# 2_BLE-T1-matrix.net
KiCad netlist of a schematic drawn in Altium Designer
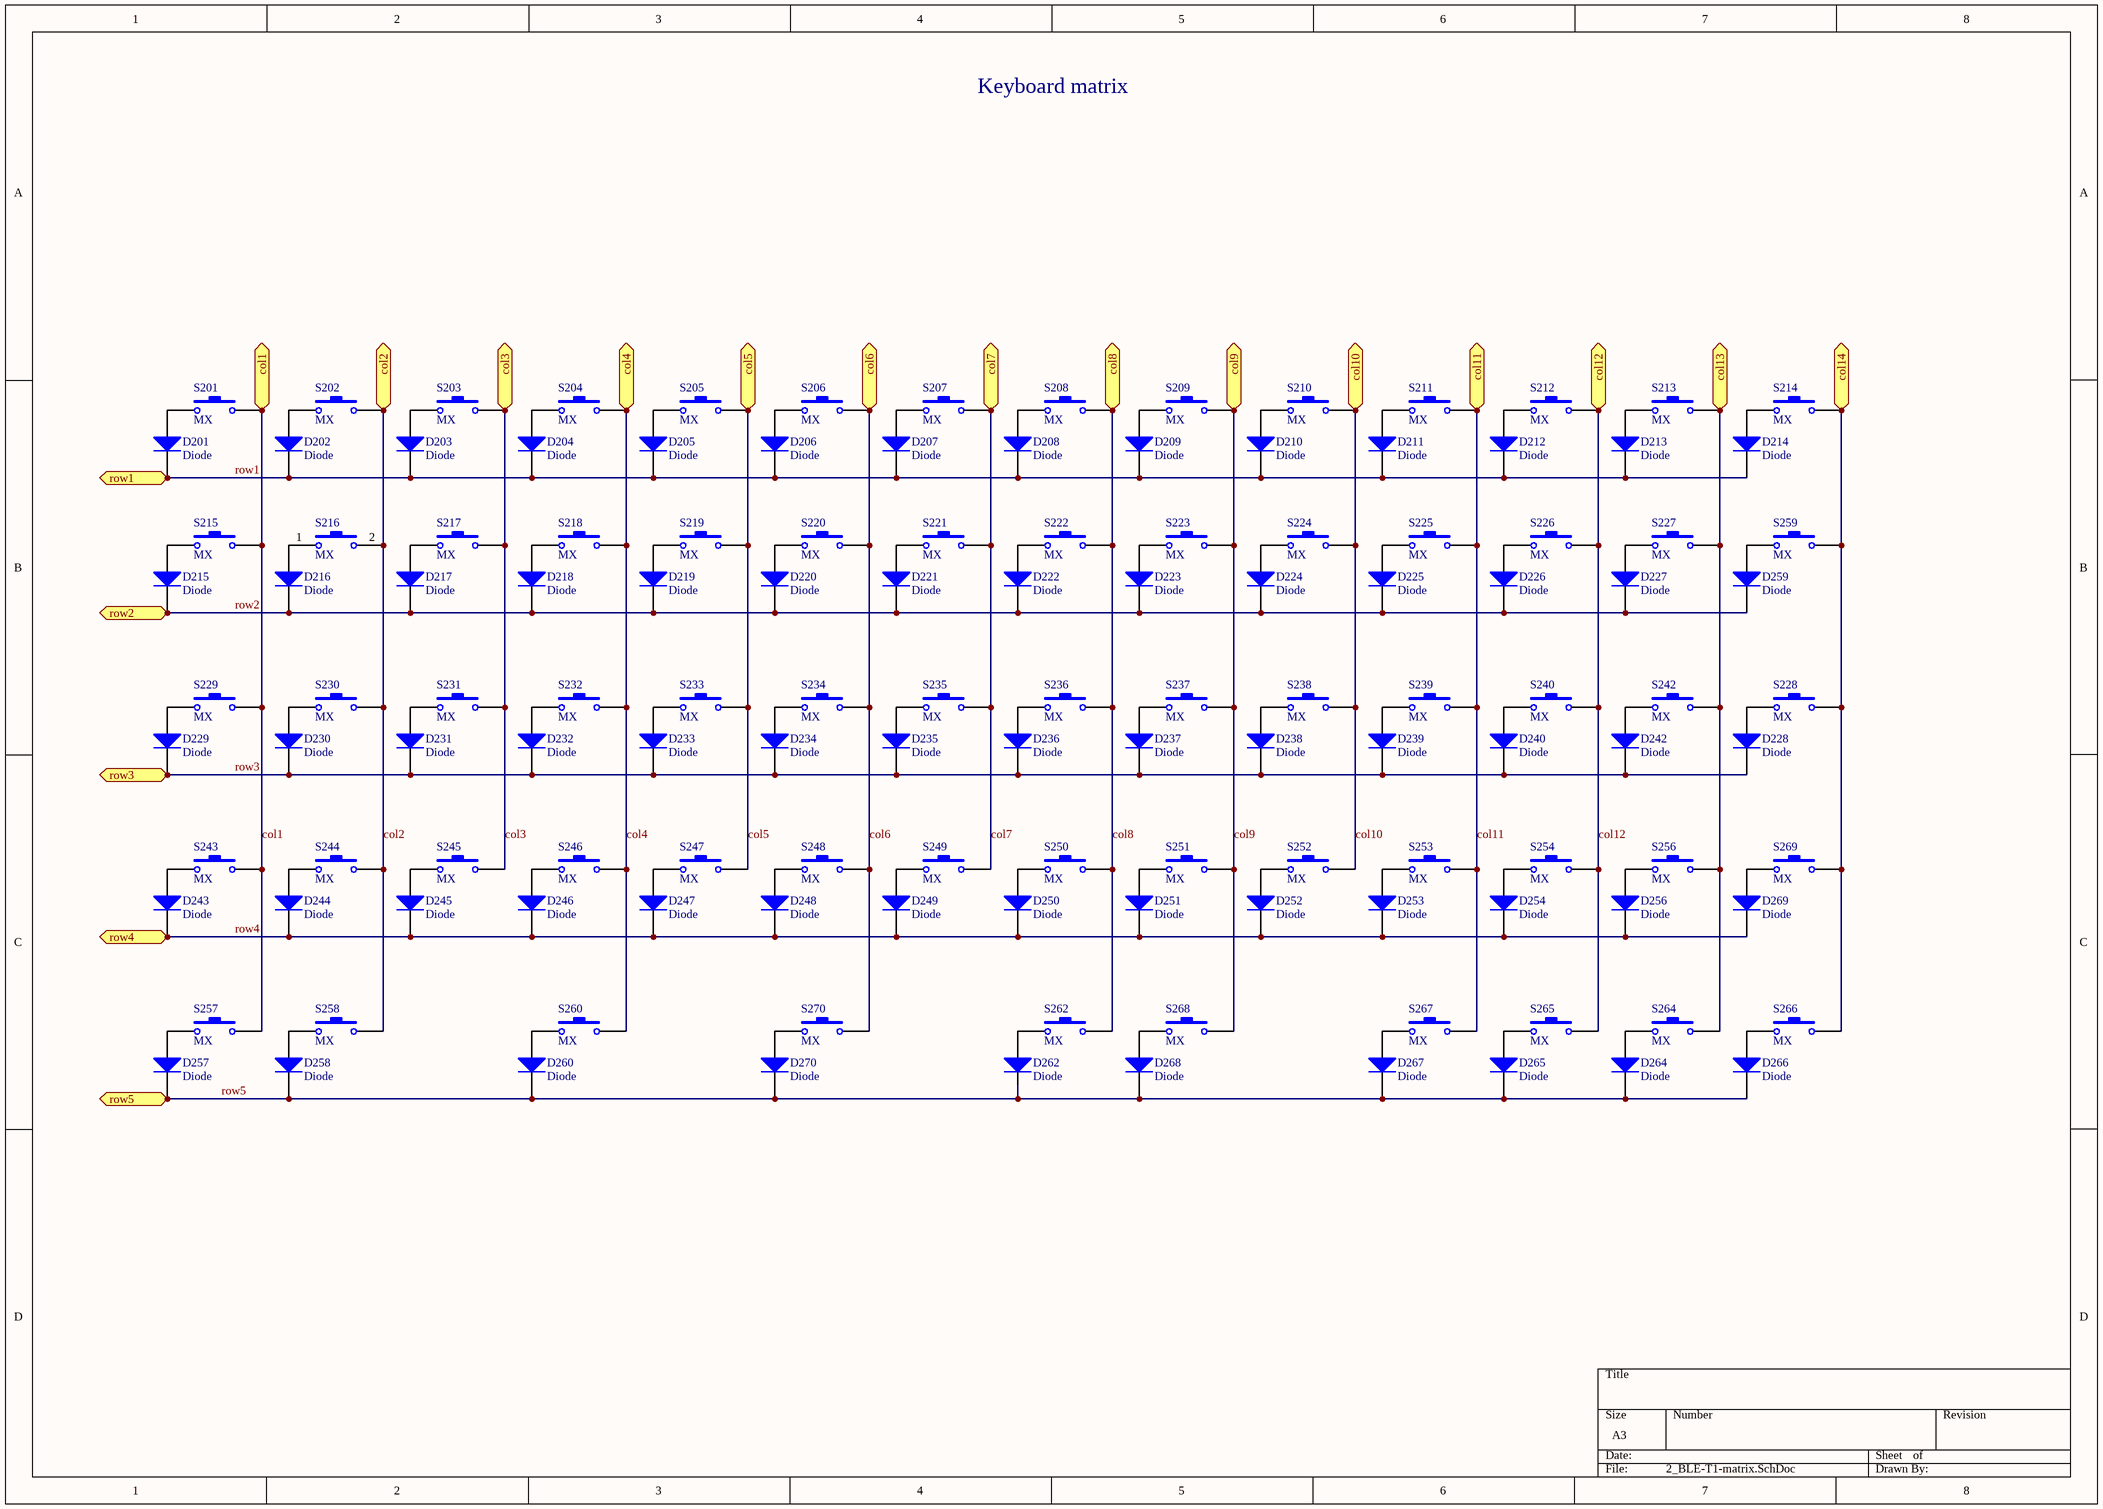
[diagram p0: 2_BLE-T1-matrix.SchDoc]

(export (version "E")
  (design (tool "Eeschema 10.0.6"))
  (components
    (comp (ref "D201")
      (value "Diode")
      (footprint "D0603[1608]")
      (description "Default Diode")
      (fields (field (name "MFG") "Bourns Inc.") (field (name "LCSC PART #") "C109002"))
      (libsource (lib "Miscellaneous Devices") (part "Diode"))
    )
    (comp (ref "D202")
      (value "Diode")
      (footprint "D0603[1608]")
      (description "Default Diode")
      (fields (field (name "MFG") "Bourns Inc.") (field (name "LCSC PART #") "C109002"))
      (libsource (lib "Miscellaneous Devices") (part "Diode"))
    )
    (comp (ref "D203")
      (value "Diode")
      (footprint "D0603[1608]")
      (description "Default Diode")
      (fields (field (name "MFG") "Bourns Inc.") (field (name "LCSC PART #") "C109002"))
      (libsource (lib "Miscellaneous Devices") (part "Diode"))
    )
    (comp (ref "D204")
      (value "Diode")
      (footprint "D0603[1608]")
      (description "Default Diode")
      (fields (field (name "MFG") "Bourns Inc.") (field (name "LCSC PART #") "C109002"))
      (libsource (lib "Miscellaneous Devices") (part "Diode"))
    )
    (comp (ref "D205")
      (value "Diode")
      (footprint "D0603[1608]")
      (description "Default Diode")
      (fields (field (name "MFG") "Bourns Inc.") (field (name "LCSC PART #") "C109002"))
      (libsource (lib "Miscellaneous Devices") (part "Diode"))
    )
    (comp (ref "D206")
      (value "Diode")
      (footprint "D0603[1608]")
      (description "Default Diode")
      (fields (field (name "MFG") "Bourns Inc.") (field (name "LCSC PART #") "C109002"))
      (libsource (lib "Miscellaneous Devices") (part "Diode"))
    )
    (comp (ref "D207")
      (value "Diode")
      (footprint "D0603[1608]")
      (description "Default Diode")
      (fields (field (name "MFG") "Bourns Inc.") (field (name "LCSC PART #") "C109002"))
      (libsource (lib "Miscellaneous Devices") (part "Diode"))
    )
    (comp (ref "D208")
      (value "Diode")
      (footprint "D0603[1608]")
      (description "Default Diode")
      (fields (field (name "MFG") "Bourns Inc.") (field (name "LCSC PART #") "C109002"))
      (libsource (lib "Miscellaneous Devices") (part "Diode"))
    )
    (comp (ref "D209")
      (value "Diode")
      (footprint "D0603[1608]")
      (description "Default Diode")
      (fields (field (name "MFG") "Bourns Inc.") (field (name "LCSC PART #") "C109002"))
      (libsource (lib "Miscellaneous Devices") (part "Diode"))
    )
    (comp (ref "D210")
      (value "Diode")
      (footprint "D0603[1608]")
      (description "Default Diode")
      (fields (field (name "MFG") "Bourns Inc.") (field (name "LCSC PART #") "C109002"))
      (libsource (lib "Miscellaneous Devices") (part "Diode"))
    )
    (comp (ref "D211")
      (value "Diode")
      (footprint "D0603[1608]")
      (description "Default Diode")
      (fields (field (name "MFG") "Bourns Inc.") (field (name "LCSC PART #") "C109002"))
      (libsource (lib "Miscellaneous Devices") (part "Diode"))
    )
    (comp (ref "D212")
      (value "Diode")
      (footprint "D0603[1608]")
      (description "Default Diode")
      (fields (field (name "MFG") "Bourns Inc.") (field (name "LCSC PART #") "C109002"))
      (libsource (lib "Miscellaneous Devices") (part "Diode"))
    )
    (comp (ref "D213")
      (value "Diode")
      (footprint "D0603[1608]")
      (description "Default Diode")
      (fields (field (name "MFG") "Bourns Inc.") (field (name "LCSC PART #") "C109002"))
      (libsource (lib "Miscellaneous Devices") (part "Diode"))
    )
    (comp (ref "D214")
      (value "Diode")
      (footprint "D0603[1608]")
      (description "Default Diode")
      (fields (field (name "MFG") "Bourns Inc.") (field (name "LCSC PART #") "C109002"))
      (libsource (lib "Miscellaneous Devices") (part "Diode"))
    )
    (comp (ref "D215")
      (value "Diode")
      (footprint "D0603[1608]")
      (description "Default Diode")
      (fields (field (name "MFG") "Bourns Inc.") (field (name "LCSC PART #") "C109002"))
      (libsource (lib "Miscellaneous Devices") (part "Diode"))
    )
    (comp (ref "D216")
      (value "Diode")
      (footprint "D0603[1608]")
      (description "Default Diode")
      (fields (field (name "MFG") "Bourns Inc.") (field (name "LCSC PART #") "C109002"))
      (libsource (lib "Miscellaneous Devices") (part "Diode"))
    )
    (comp (ref "D217")
      (value "Diode")
      (footprint "D0603[1608]")
      (description "Default Diode")
      (fields (field (name "MFG") "Bourns Inc.") (field (name "LCSC PART #") "C109002"))
      (libsource (lib "Miscellaneous Devices") (part "Diode"))
    )
    (comp (ref "D218")
      (value "Diode")
      (footprint "D0603[1608]")
      (description "Default Diode")
      (fields (field (name "MFG") "Bourns Inc.") (field (name "LCSC PART #") "C109002"))
      (libsource (lib "Miscellaneous Devices") (part "Diode"))
    )
    (comp (ref "D219")
      (value "Diode")
      (footprint "D0603[1608]")
      (description "Default Diode")
      (fields (field (name "MFG") "Bourns Inc.") (field (name "LCSC PART #") "C109002"))
      (libsource (lib "Miscellaneous Devices") (part "Diode"))
    )
    (comp (ref "D220")
      (value "Diode")
      (footprint "D0603[1608]")
      (description "Default Diode")
      (fields (field (name "MFG") "Bourns Inc.") (field (name "LCSC PART #") "C109002"))
      (libsource (lib "Miscellaneous Devices") (part "Diode"))
    )
    (comp (ref "D221")
      (value "Diode")
      (footprint "D0603[1608]")
      (description "Default Diode")
      (fields (field (name "MFG") "Bourns Inc.") (field (name "LCSC PART #") "C109002"))
      (libsource (lib "Miscellaneous Devices") (part "Diode"))
    )
    (comp (ref "D222")
      (value "Diode")
      (footprint "D0603[1608]")
      (description "Default Diode")
      (fields (field (name "MFG") "Bourns Inc.") (field (name "LCSC PART #") "C109002"))
      (libsource (lib "Miscellaneous Devices") (part "Diode"))
    )
    (comp (ref "D223")
      (value "Diode")
      (footprint "D0603[1608]")
      (description "Default Diode")
      (fields (field (name "MFG") "Bourns Inc.") (field (name "LCSC PART #") "C109002"))
      (libsource (lib "Miscellaneous Devices") (part "Diode"))
    )
    (comp (ref "D224")
      (value "Diode")
      (footprint "D0603[1608]")
      (description "Default Diode")
      (fields (field (name "MFG") "Bourns Inc.") (field (name "LCSC PART #") "C109002"))
      (libsource (lib "Miscellaneous Devices") (part "Diode"))
    )
    (comp (ref "D225")
      (value "Diode")
      (footprint "D0603[1608]")
      (description "Default Diode")
      (fields (field (name "MFG") "Bourns Inc.") (field (name "LCSC PART #") "C109002"))
      (libsource (lib "Miscellaneous Devices") (part "Diode"))
    )
    (comp (ref "D226")
      (value "Diode")
      (footprint "D0603[1608]")
      (description "Default Diode")
      (fields (field (name "MFG") "Bourns Inc.") (field (name "LCSC PART #") "C109002"))
      (libsource (lib "Miscellaneous Devices") (part "Diode"))
    )
    (comp (ref "D227")
      (value "Diode")
      (footprint "D0603[1608]")
      (description "Default Diode")
      (fields (field (name "MFG") "Bourns Inc.") (field (name "LCSC PART #") "C109002"))
      (libsource (lib "Miscellaneous Devices") (part "Diode"))
    )
    (comp (ref "D228")
      (value "Diode")
      (footprint "D0603[1608]")
      (description "Default Diode")
      (fields (field (name "MFG") "Bourns Inc.") (field (name "LCSC PART #") "C109002"))
      (libsource (lib "Miscellaneous Devices") (part "Diode"))
    )
    (comp (ref "D229")
      (value "Diode")
      (footprint "D0603[1608]")
      (description "Default Diode")
      (fields (field (name "MFG") "Bourns Inc.") (field (name "LCSC PART #") "C109002"))
      (libsource (lib "Miscellaneous Devices") (part "Diode"))
    )
    (comp (ref "D230")
      (value "Diode")
      (footprint "D0603[1608]")
      (description "Default Diode")
      (fields (field (name "MFG") "Bourns Inc.") (field (name "LCSC PART #") "C109002"))
      (libsource (lib "Miscellaneous Devices") (part "Diode"))
    )
    (comp (ref "D231")
      (value "Diode")
      (footprint "D0603[1608]")
      (description "Default Diode")
      (fields (field (name "MFG") "Bourns Inc.") (field (name "LCSC PART #") "C109002"))
      (libsource (lib "Miscellaneous Devices") (part "Diode"))
    )
    (comp (ref "D232")
      (value "Diode")
      (footprint "D0603[1608]")
      (description "Default Diode")
      (fields (field (name "MFG") "Bourns Inc.") (field (name "LCSC PART #") "C109002"))
      (libsource (lib "Miscellaneous Devices") (part "Diode"))
    )
    (comp (ref "D233")
      (value "Diode")
      (footprint "D0603[1608]")
      (description "Default Diode")
      (fields (field (name "MFG") "Bourns Inc.") (field (name "LCSC PART #") "C109002"))
      (libsource (lib "Miscellaneous Devices") (part "Diode"))
    )
    (comp (ref "D234")
      (value "Diode")
      (footprint "D0603[1608]")
      (description "Default Diode")
      (fields (field (name "MFG") "Bourns Inc.") (field (name "LCSC PART #") "C109002"))
      (libsource (lib "Miscellaneous Devices") (part "Diode"))
    )
    (comp (ref "D235")
      (value "Diode")
      (footprint "D0603[1608]")
      (description "Default Diode")
      (fields (field (name "MFG") "Bourns Inc.") (field (name "LCSC PART #") "C109002"))
      (libsource (lib "Miscellaneous Devices") (part "Diode"))
    )
    (comp (ref "D236")
      (value "Diode")
      (footprint "D0603[1608]")
      (description "Default Diode")
      (fields (field (name "MFG") "Bourns Inc.") (field (name "LCSC PART #") "C109002"))
      (libsource (lib "Miscellaneous Devices") (part "Diode"))
    )
    (comp (ref "D237")
      (value "Diode")
      (footprint "D0603[1608]")
      (description "Default Diode")
      (fields (field (name "MFG") "Bourns Inc.") (field (name "LCSC PART #") "C109002"))
      (libsource (lib "Miscellaneous Devices") (part "Diode"))
    )
    (comp (ref "D238")
      (value "Diode")
      (footprint "D0603[1608]")
      (description "Default Diode")
      (fields (field (name "MFG") "Bourns Inc.") (field (name "LCSC PART #") "C109002"))
      (libsource (lib "Miscellaneous Devices") (part "Diode"))
    )
    (comp (ref "D239")
      (value "Diode")
      (footprint "D0603[1608]")
      (description "Default Diode")
      (fields (field (name "MFG") "Bourns Inc.") (field (name "LCSC PART #") "C109002"))
      (libsource (lib "Miscellaneous Devices") (part "Diode"))
    )
    (comp (ref "D240")
      (value "Diode")
      (footprint "D0603[1608]")
      (description "Default Diode")
      (fields (field (name "MFG") "Bourns Inc.") (field (name "LCSC PART #") "C109002"))
      (libsource (lib "Miscellaneous Devices") (part "Diode"))
    )
    (comp (ref "D242")
      (value "Diode")
      (footprint "D0603[1608]")
      (description "Default Diode")
      (fields (field (name "MFG") "Bourns Inc.") (field (name "LCSC PART #") "C109002"))
      (libsource (lib "Miscellaneous Devices") (part "Diode"))
    )
    (comp (ref "D243")
      (value "Diode")
      (footprint "D0603[1608]")
      (description "Default Diode")
      (fields (field (name "MFG") "Bourns Inc.") (field (name "LCSC PART #") "C109002"))
      (libsource (lib "Miscellaneous Devices") (part "Diode"))
    )
    (comp (ref "D244")
      (value "Diode")
      (footprint "D0603[1608]")
      (description "Default Diode")
      (fields (field (name "MFG") "Bourns Inc.") (field (name "LCSC PART #") "C109002"))
      (libsource (lib "Miscellaneous Devices") (part "Diode"))
    )
    (comp (ref "D245")
      (value "Diode")
      (footprint "D0603[1608]")
      (description "Default Diode")
      (fields (field (name "MFG") "Bourns Inc.") (field (name "LCSC PART #") "C109002"))
      (libsource (lib "Miscellaneous Devices") (part "Diode"))
    )
    (comp (ref "D246")
      (value "Diode")
      (footprint "D0603[1608]")
      (description "Default Diode")
      (fields (field (name "MFG") "Bourns Inc.") (field (name "LCSC PART #") "C109002"))
      (libsource (lib "Miscellaneous Devices") (part "Diode"))
    )
    (comp (ref "D247")
      (value "Diode")
      (footprint "D0603[1608]")
      (description "Default Diode")
      (fields (field (name "MFG") "Bourns Inc.") (field (name "LCSC PART #") "C109002"))
      (libsource (lib "Miscellaneous Devices") (part "Diode"))
    )
    (comp (ref "D248")
      (value "Diode")
      (footprint "D0603[1608]")
      (description "Default Diode")
      (fields (field (name "MFG") "Bourns Inc.") (field (name "LCSC PART #") "C109002"))
      (libsource (lib "Miscellaneous Devices") (part "Diode"))
    )
    (comp (ref "D249")
      (value "Diode")
      (footprint "D0603[1608]")
      (description "Default Diode")
      (fields (field (name "MFG") "Bourns Inc.") (field (name "LCSC PART #") "C109002"))
      (libsource (lib "Miscellaneous Devices") (part "Diode"))
    )
    (comp (ref "D250")
      (value "Diode")
      (footprint "D0603[1608]")
      (description "Default Diode")
      (fields (field (name "MFG") "Bourns Inc.") (field (name "LCSC PART #") "C109002"))
      (libsource (lib "Miscellaneous Devices") (part "Diode"))
    )
    (comp (ref "D251")
      (value "Diode")
      (footprint "D0603[1608]")
      (description "Default Diode")
      (fields (field (name "MFG") "Bourns Inc.") (field (name "LCSC PART #") "C109002"))
      (libsource (lib "Miscellaneous Devices") (part "Diode"))
    )
    (comp (ref "D252")
      (value "Diode")
      (footprint "D0603[1608]")
      (description "Default Diode")
      (fields (field (name "MFG") "Bourns Inc.") (field (name "LCSC PART #") "C109002"))
      (libsource (lib "Miscellaneous Devices") (part "Diode"))
    )
    (comp (ref "D253")
      (value "Diode")
      (footprint "D0603[1608]")
      (description "Default Diode")
      (fields (field (name "MFG") "Bourns Inc.") (field (name "LCSC PART #") "C109002"))
      (libsource (lib "Miscellaneous Devices") (part "Diode"))
    )
    (comp (ref "D254")
      (value "Diode")
      (footprint "D0603[1608]")
      (description "Default Diode")
      (fields (field (name "MFG") "Bourns Inc.") (field (name "LCSC PART #") "C109002"))
      (libsource (lib "Miscellaneous Devices") (part "Diode"))
    )
    (comp (ref "D256")
      (value "Diode")
      (footprint "D0603[1608]")
      (description "Default Diode")
      (fields (field (name "MFG") "Bourns Inc.") (field (name "LCSC PART #") "C109002"))
      (libsource (lib "Miscellaneous Devices") (part "Diode"))
    )
    (comp (ref "D257")
      (value "Diode")
      (footprint "D0603[1608]")
      (description "Default Diode")
      (fields (field (name "MFG") "Bourns Inc.") (field (name "LCSC PART #") "C109002"))
      (libsource (lib "Miscellaneous Devices") (part "Diode"))
    )
    (comp (ref "D258")
      (value "Diode")
      (footprint "D0603[1608]")
      (description "Default Diode")
      (fields (field (name "MFG") "Bourns Inc.") (field (name "LCSC PART #") "C109002"))
      (libsource (lib "Miscellaneous Devices") (part "Diode"))
    )
    (comp (ref "D259")
      (value "Diode")
      (footprint "D0603[1608]")
      (description "Default Diode")
      (fields (field (name "MFG") "Bourns Inc.") (field (name "LCSC PART #") "C109002"))
      (libsource (lib "Miscellaneous Devices") (part "Diode"))
    )
    (comp (ref "D260")
      (value "Diode")
      (footprint "D0603[1608]")
      (description "Default Diode")
      (fields (field (name "MFG") "Bourns Inc.") (field (name "LCSC PART #") "C109002"))
      (libsource (lib "Miscellaneous Devices") (part "Diode"))
    )
    (comp (ref "D262")
      (value "Diode")
      (footprint "D0603[1608]")
      (description "Default Diode")
      (fields (field (name "MFG") "Bourns Inc.") (field (name "LCSC PART #") "C109002"))
      (libsource (lib "Miscellaneous Devices") (part "Diode"))
    )
    (comp (ref "D264")
      (value "Diode")
      (footprint "D0603[1608]")
      (description "Default Diode")
      (fields (field (name "MFG") "Bourns Inc.") (field (name "LCSC PART #") "C109002"))
      (libsource (lib "Miscellaneous Devices") (part "Diode"))
    )
    (comp (ref "D265")
      (value "Diode")
      (footprint "D0603[1608]")
      (description "Default Diode")
      (fields (field (name "MFG") "Bourns Inc.") (field (name "LCSC PART #") "C109002"))
      (libsource (lib "Miscellaneous Devices") (part "Diode"))
    )
    (comp (ref "D266")
      (value "Diode")
      (footprint "D0603[1608]")
      (description "Default Diode")
      (fields (field (name "MFG") "Bourns Inc.") (field (name "LCSC PART #") "C109002"))
      (libsource (lib "Miscellaneous Devices") (part "Diode"))
    )
    (comp (ref "D267")
      (value "Diode")
      (footprint "D0603[1608]")
      (description "Default Diode")
      (fields (field (name "MFG") "Bourns Inc.") (field (name "LCSC PART #") "C109002"))
      (libsource (lib "Miscellaneous Devices") (part "Diode"))
    )
    (comp (ref "D268")
      (value "Diode")
      (footprint "D0603[1608]")
      (description "Default Diode")
      (fields (field (name "MFG") "Bourns Inc.") (field (name "LCSC PART #") "C109002"))
      (libsource (lib "Miscellaneous Devices") (part "Diode"))
    )
    (comp (ref "D269")
      (value "Diode")
      (footprint "D0603[1608]")
      (description "Default Diode")
      (fields (field (name "MFG") "Bourns Inc.") (field (name "LCSC PART #") "C109002"))
      (libsource (lib "Miscellaneous Devices") (part "Diode"))
    )
    (comp (ref "D270")
      (value "Diode")
      (footprint "D0603[1608]")
      (description "Default Diode")
      (fields (field (name "MFG") "Bourns Inc.") (field (name "LCSC PART #") "C109002"))
      (libsource (lib "Miscellaneous Devices") (part "Diode"))
    )
    (comp (ref "S201")
      (value "MX")
      (footprint "MX-switch - switched pol")
      (description "Switch")
      (libsource (lib "Miscellaneous Devices") (part "SW-PB"))
    )
    (comp (ref "S202")
      (value "MX")
      (footprint "MX-switch - switched pol - connector")
      (description "Switch")
      (libsource (lib "Miscellaneous Devices") (part "SW-PB"))
    )
    (comp (ref "S203")
      (value "MX")
      (footprint "MX-switch - switched pol")
      (description "Switch")
      (libsource (lib "Miscellaneous Devices") (part "SW-PB"))
    )
    (comp (ref "S204")
      (value "MX")
      (footprint "MX-switch - switched pol")
      (description "Switch")
      (libsource (lib "Miscellaneous Devices") (part "SW-PB"))
    )
    (comp (ref "S205")
      (value "MX")
      (footprint "MX-switch - switched pol")
      (description "Switch")
      (libsource (lib "Miscellaneous Devices") (part "SW-PB"))
    )
    (comp (ref "S206")
      (value "MX")
      (footprint "MX-switch - switched pol")
      (description "Switch")
      (libsource (lib "Miscellaneous Devices") (part "SW-PB"))
    )
    (comp (ref "S207")
      (value "MX")
      (footprint "MX-switch - switched pol")
      (description "Switch")
      (libsource (lib "Miscellaneous Devices") (part "SW-PB"))
    )
    (comp (ref "S208")
      (value "MX")
      (footprint "MX-switch - switched pol")
      (description "Switch")
      (libsource (lib "Miscellaneous Devices") (part "SW-PB"))
    )
    (comp (ref "S209")
      (value "MX")
      (footprint "MX-switch - switched pol")
      (description "Switch")
      (libsource (lib "Miscellaneous Devices") (part "SW-PB"))
    )
    (comp (ref "S210")
      (value "MX")
      (footprint "MX-switch - switched pol")
      (description "Switch")
      (libsource (lib "Miscellaneous Devices") (part "SW-PB"))
    )
    (comp (ref "S211")
      (value "MX")
      (footprint "MX-switch - switched pol")
      (description "Switch")
      (libsource (lib "Miscellaneous Devices") (part "SW-PB"))
    )
    (comp (ref "S212")
      (value "MX")
      (footprint "MX-switch - switched pol")
      (description "Switch")
      (libsource (lib "Miscellaneous Devices") (part "SW-PB"))
    )
    (comp (ref "S213")
      (value "MX")
      (footprint "MX-switch - switched pol")
      (description "Switch")
      (libsource (lib "Miscellaneous Devices") (part "SW-PB"))
    )
    (comp (ref "S214")
      (value "MX")
      (footprint "MX-switch - switched pol")
      (description "Switch")
      (libsource (lib "Miscellaneous Devices") (part "SW-PB"))
    )
    (comp (ref "S215")
      (value "MX")
      (footprint "MX-switch - 1.5U")
      (description "TAB")
      (libsource (lib "Miscellaneous Devices") (part "SW-PB"))
    )
    (comp (ref "S216")
      (value "MX")
      (footprint "MX-switch - switched pol")
      (description "Switch")
      (libsource (lib "") (part "SW-PB_1"))
    )
    (comp (ref "S217")
      (value "MX")
      (footprint "MX-switch - switched pol")
      (description "Switch")
      (libsource (lib "Miscellaneous Devices") (part "SW-PB"))
    )
    (comp (ref "S218")
      (value "MX")
      (footprint "MX-switch - switched pol")
      (description "Switch")
      (libsource (lib "Miscellaneous Devices") (part "SW-PB"))
    )
    (comp (ref "S219")
      (value "MX")
      (footprint "MX-switch - switched pol")
      (description "Switch")
      (libsource (lib "Miscellaneous Devices") (part "SW-PB"))
    )
    (comp (ref "S220")
      (value "MX")
      (footprint "MX-switch - switched pol")
      (description "Switch")
      (libsource (lib "Miscellaneous Devices") (part "SW-PB"))
    )
    (comp (ref "S221")
      (value "MX")
      (footprint "MX-switch - switched pol")
      (description "Switch")
      (libsource (lib "Miscellaneous Devices") (part "SW-PB"))
    )
    (comp (ref "S222")
      (value "MX")
      (footprint "MX-switch - switched pol")
      (description "Switch")
      (libsource (lib "Miscellaneous Devices") (part "SW-PB"))
    )
    (comp (ref "S223")
      (value "MX")
      (footprint "MX-switch - switched pol")
      (description "Switch")
      (libsource (lib "Miscellaneous Devices") (part "SW-PB"))
    )
    (comp (ref "S224")
      (value "MX")
      (footprint "MX-switch - switched pol")
      (description "Switch")
      (libsource (lib "Miscellaneous Devices") (part "SW-PB"))
    )
    (comp (ref "S225")
      (value "MX")
      (footprint "MX-switch - switched pol")
      (description "Switch")
      (libsource (lib "Miscellaneous Devices") (part "SW-PB"))
    )
    (comp (ref "S226")
      (value "MX")
      (footprint "MX-switch - switched pol")
      (description "Switch")
      (libsource (lib "Miscellaneous Devices") (part "SW-PB"))
    )
    (comp (ref "S227")
      (value "MX")
      (footprint "MX-switch - switched pol")
      (description "Switch")
      (libsource (lib "Miscellaneous Devices") (part "SW-PB"))
    )
    (comp (ref "S228")
      (value "MX")
      (footprint "MX-switch - PIPE_ISO_ENTER")
      (description "Switch")
      (libsource (lib "Miscellaneous Devices") (part "SW-PB"))
    )
    (comp (ref "S229")
      (value "MX")
      (footprint "MX-switch - CAPS")
      (description "Switch")
      (libsource (lib "Miscellaneous Devices") (part "SW-PB"))
    )
    (comp (ref "S230")
      (value "MX")
      (footprint "MX-switch - switched pol")
      (description "Switch")
      (libsource (lib "Miscellaneous Devices") (part "SW-PB"))
    )
    (comp (ref "S231")
      (value "MX")
      (footprint "MX-switch - switched pol")
      (description "Switch")
      (libsource (lib "Miscellaneous Devices") (part "SW-PB"))
    )
    (comp (ref "S232")
      (value "MX")
      (footprint "MX-switch - switched pol")
      (description "Switch")
      (libsource (lib "Miscellaneous Devices") (part "SW-PB"))
    )
    (comp (ref "S233")
      (value "MX")
      (footprint "MX-switch - switched pol")
      (description "Switch")
      (libsource (lib "Miscellaneous Devices") (part "SW-PB"))
    )
    (comp (ref "S234")
      (value "MX")
      (footprint "MX-switch - switched pol")
      (description "Switch")
      (libsource (lib "Miscellaneous Devices") (part "SW-PB"))
    )
    (comp (ref "S235")
      (value "MX")
      (footprint "MX-switch - switched pol")
      (description "Switch")
      (libsource (lib "Miscellaneous Devices") (part "SW-PB"))
    )
    (comp (ref "S236")
      (value "MX")
      (footprint "MX-switch - switched pol")
      (description "Switch")
      (libsource (lib "Miscellaneous Devices") (part "SW-PB"))
    )
    (comp (ref "S237")
      (value "MX")
      (footprint "MX-switch - switched pol")
      (description "Switch")
      (libsource (lib "Miscellaneous Devices") (part "SW-PB"))
    )
    (comp (ref "S238")
      (value "MX")
      (footprint "MX-switch - switched pol")
      (description "Switch")
      (libsource (lib "Miscellaneous Devices") (part "SW-PB"))
    )
    (comp (ref "S239")
      (value "MX")
      (footprint "MX-switch - switched pol")
      (description "Switch")
      (libsource (lib "Miscellaneous Devices") (part "SW-PB"))
    )
    (comp (ref "S240")
      (value "MX")
      (footprint "MX-switch - switched pol")
      (description "Switch")
      (libsource (lib "Miscellaneous Devices") (part "SW-PB"))
    )
    (comp (ref "S242")
      (value "MX")
      (footprint "MX-switch - Enter_ANSI_ISO_KEY")
      (description "Switch")
      (libsource (lib "Miscellaneous Devices") (part "SW-PB"))
    )
    (comp (ref "S243")
      (value "MX")
      (footprint "MX-switch - Left shift")
      (description "Switch")
      (libsource (lib "Miscellaneous Devices") (part "SW-PB"))
    )
    (comp (ref "S244")
      (value "MX")
      (footprint "MX-switch")
      (description "Switch")
      (libsource (lib "Miscellaneous Devices") (part "SW-PB"))
    )
    (comp (ref "S245")
      (value "MX")
      (footprint "MX-switch - switched pol")
      (description "Switch")
      (libsource (lib "Miscellaneous Devices") (part "SW-PB"))
    )
    (comp (ref "S246")
      (value "MX")
      (footprint "MX-switch - switched pol")
      (description "Switch")
      (libsource (lib "Miscellaneous Devices") (part "SW-PB"))
    )
    (comp (ref "S247")
      (value "MX")
      (footprint "MX-switch - switched pol")
      (description "Switch")
      (libsource (lib "Miscellaneous Devices") (part "SW-PB"))
    )
    (comp (ref "S248")
      (value "MX")
      (footprint "MX-switch - switched pol")
      (description "Switch")
      (libsource (lib "Miscellaneous Devices") (part "SW-PB"))
    )
    (comp (ref "S249")
      (value "MX")
      (footprint "MX-switch - switched pol")
      (description "Switch")
      (libsource (lib "Miscellaneous Devices") (part "SW-PB"))
    )
    (comp (ref "S250")
      (value "MX")
      (footprint "MX-switch - switched pol")
      (description "Switch")
      (libsource (lib "Miscellaneous Devices") (part "SW-PB"))
    )
    (comp (ref "S251")
      (value "MX")
      (footprint "MX-switch - switched pol")
      (description "Switch")
      (libsource (lib "Miscellaneous Devices") (part "SW-PB"))
    )
    (comp (ref "S252")
      (value "MX")
      (footprint "MX-switch - switched pol")
      (description "Switch")
      (libsource (lib "Miscellaneous Devices") (part "SW-PB"))
    )
    (comp (ref "S253")
      (value "MX")
      (footprint "MX-switch - switched pol")
      (description "Switch")
      (libsource (lib "Miscellaneous Devices") (part "SW-PB"))
    )
    (comp (ref "S254")
      (value "MX")
      (footprint "MX-switch - switched pol")
      (description "Switch")
      (libsource (lib "Miscellaneous Devices") (part "SW-PB"))
    )
    (comp (ref "S256")
      (value "MX")
      (footprint "MX-switch - right shift")
      (description "Switch")
      (libsource (lib "Miscellaneous Devices") (part "SW-PB"))
    )
    (comp (ref "S257")
      (value "MX")
      (footprint "MX-switch - 1.5u MOD-L")
      (description "Switch")
      (libsource (lib "Miscellaneous Devices") (part "SW-PB"))
    )
    (comp (ref "S258")
      (value "MX")
      (footprint "MX-switch - 1u MOD-L")
      (description "Switch")
      (libsource (lib "Miscellaneous Devices") (part "SW-PB"))
    )
    (comp (ref "S259")
      (value "MX")
      (footprint "MX-switch - backspace")
      (description "Switch")
      (libsource (lib "Miscellaneous Devices") (part "SW-PB"))
    )
    (comp (ref "S260")
      (value "MX")
      (footprint "MX-switch - 1.5u MOD-L")
      (description "Switch")
      (libsource (lib "Miscellaneous Devices") (part "SW-PB"))
    )
    (comp (ref "S262")
      (value "MX")
      (footprint "MX-switch - Space_V3")
      (description "Switch")
      (libsource (lib "Miscellaneous Devices") (part "SW-PB"))
    )
    (comp (ref "S264")
      (value "MX")
      (footprint "MX-switch - 1u MOD-R")
      (description "Switch")
      (libsource (lib "Miscellaneous Devices") (part "SW-PB"))
    )
    (comp (ref "S265")
      (value "MX")
      (footprint "MX-switch - 1.5u MOD-R")
      (description "Switch")
      (libsource (lib "Miscellaneous Devices") (part "SW-PB"))
    )
    (comp (ref "S266")
      (value "MX")
      (footprint "MX-switch - 1.5u MOD-R")
      (description "Switch")
      (libsource (lib "Miscellaneous Devices") (part "SW-PB"))
    )
    (comp (ref "S267")
      (value "MX")
      (footprint "MX-switch")
      (description "Switch")
      (libsource (lib "Miscellaneous Devices") (part "SW-PB"))
    )
    (comp (ref "S268")
      (value "MX")
      (footprint "MX-switch - R split space_V2")
      (description "Switch")
      (libsource (lib "Miscellaneous Devices") (part "SW-PB"))
    )
    (comp (ref "S269")
      (value "MX")
      (footprint "MX-switch")
      (description "Switch")
      (libsource (lib "Miscellaneous Devices") (part "SW-PB"))
    )
    (comp (ref "S270")
      (value "MX")
      (footprint "MX-switch - L split space_V2")
      (description "Switch")
      (libsource (lib "Miscellaneous Devices") (part "SW-PB"))
    )
  )
  (nets
    (net (code "1") (name "/col1") (class "Default")
      (node (ref "S201") (pin "2") (pinfunction "2_2") (pintype "passive"))
      (node (ref "S215") (pin "2") (pinfunction "2_2") (pintype "passive"))
      (node (ref "S229") (pin "2") (pinfunction "2_2") (pintype "passive"))
      (node (ref "S243") (pin "2") (pinfunction "2_2") (pintype "passive"))
      (node (ref "S257") (pin "2") (pinfunction "2_2") (pintype "passive"))
    )
    (net (code "2") (name "/col2") (class "Default")
      (node (ref "S202") (pin "2") (pinfunction "2_2") (pintype "passive"))
      (node (ref "S216") (pin "2") (pinfunction "2_2") (pintype "passive"))
      (node (ref "S230") (pin "2") (pinfunction "2_2") (pintype "passive"))
      (node (ref "S244") (pin "2") (pinfunction "2_2") (pintype "passive"))
      (node (ref "S258") (pin "2") (pinfunction "2_2") (pintype "passive"))
    )
    (net (code "3") (name "/col3") (class "Default")
      (node (ref "S203") (pin "2") (pinfunction "2_2") (pintype "passive"))
      (node (ref "S217") (pin "2") (pinfunction "2_2") (pintype "passive"))
      (node (ref "S231") (pin "2") (pinfunction "2_2") (pintype "passive"))
      (node (ref "S245") (pin "2") (pinfunction "2_2") (pintype "passive"))
    )
    (net (code "4") (name "/col4") (class "Default")
      (node (ref "S204") (pin "2") (pinfunction "2_2") (pintype "passive"))
      (node (ref "S218") (pin "2") (pinfunction "2_2") (pintype "passive"))
      (node (ref "S232") (pin "2") (pinfunction "2_2") (pintype "passive"))
      (node (ref "S246") (pin "2") (pinfunction "2_2") (pintype "passive"))
      (node (ref "S260") (pin "2") (pinfunction "2_2") (pintype "passive"))
    )
    (net (code "5") (name "/col5") (class "Default")
      (node (ref "S205") (pin "2") (pinfunction "2_2") (pintype "passive"))
      (node (ref "S219") (pin "2") (pinfunction "2_2") (pintype "passive"))
      (node (ref "S233") (pin "2") (pinfunction "2_2") (pintype "passive"))
      (node (ref "S247") (pin "2") (pinfunction "2_2") (pintype "passive"))
    )
    (net (code "6") (name "/col6") (class "Default")
      (node (ref "S206") (pin "2") (pinfunction "2_2") (pintype "passive"))
      (node (ref "S220") (pin "2") (pinfunction "2_2") (pintype "passive"))
      (node (ref "S234") (pin "2") (pinfunction "2_2") (pintype "passive"))
      (node (ref "S248") (pin "2") (pinfunction "2_2") (pintype "passive"))
      (node (ref "S270") (pin "2") (pinfunction "2_2") (pintype "passive"))
    )
    (net (code "7") (name "/col7") (class "Default")
      (node (ref "S207") (pin "2") (pinfunction "2_2") (pintype "passive"))
      (node (ref "S221") (pin "2") (pinfunction "2_2") (pintype "passive"))
      (node (ref "S235") (pin "2") (pinfunction "2_2") (pintype "passive"))
      (node (ref "S249") (pin "2") (pinfunction "2_2") (pintype "passive"))
    )
    (net (code "8") (name "/col8") (class "Default")
      (node (ref "S208") (pin "2") (pinfunction "2_2") (pintype "passive"))
      (node (ref "S222") (pin "2") (pinfunction "2_2") (pintype "passive"))
      (node (ref "S236") (pin "2") (pinfunction "2_2") (pintype "passive"))
      (node (ref "S250") (pin "2") (pinfunction "2_2") (pintype "passive"))
      (node (ref "S262") (pin "2") (pinfunction "2_2") (pintype "passive"))
    )
    (net (code "9") (name "/col9") (class "Default")
      (node (ref "S209") (pin "2") (pinfunction "2_2") (pintype "passive"))
      (node (ref "S223") (pin "2") (pinfunction "2_2") (pintype "passive"))
      (node (ref "S237") (pin "2") (pinfunction "2_2") (pintype "passive"))
      (node (ref "S251") (pin "2") (pinfunction "2_2") (pintype "passive"))
      (node (ref "S268") (pin "2") (pinfunction "2_2") (pintype "passive"))
    )
    (net (code "10") (name "/col10") (class "Default")
      (node (ref "S210") (pin "2") (pinfunction "2_2") (pintype "passive"))
      (node (ref "S224") (pin "2") (pinfunction "2_2") (pintype "passive"))
      (node (ref "S238") (pin "2") (pinfunction "2_2") (pintype "passive"))
      (node (ref "S252") (pin "2") (pinfunction "2_2") (pintype "passive"))
    )
    (net (code "11") (name "/col11") (class "Default")
      (node (ref "S211") (pin "2") (pinfunction "2_2") (pintype "passive"))
      (node (ref "S225") (pin "2") (pinfunction "2_2") (pintype "passive"))
      (node (ref "S239") (pin "2") (pinfunction "2_2") (pintype "passive"))
      (node (ref "S253") (pin "2") (pinfunction "2_2") (pintype "passive"))
      (node (ref "S267") (pin "2") (pinfunction "2_2") (pintype "passive"))
    )
    (net (code "12") (name "/col12") (class "Default")
      (node (ref "S212") (pin "2") (pinfunction "2_2") (pintype "passive"))
      (node (ref "S226") (pin "2") (pinfunction "2_2") (pintype "passive"))
      (node (ref "S240") (pin "2") (pinfunction "2_2") (pintype "passive"))
      (node (ref "S254") (pin "2") (pinfunction "2_2") (pintype "passive"))
      (node (ref "S265") (pin "2") (pinfunction "2_2") (pintype "passive"))
    )
    (net (code "13") (name "/col13") (class "Default")
      (node (ref "S213") (pin "2") (pinfunction "2_2") (pintype "passive"))
      (node (ref "S227") (pin "2") (pinfunction "2_2") (pintype "passive"))
      (node (ref "S242") (pin "2") (pinfunction "2_2") (pintype "passive"))
      (node (ref "S256") (pin "2") (pinfunction "2_2") (pintype "passive"))
      (node (ref "S264") (pin "2") (pinfunction "2_2") (pintype "passive"))
    )
    (net (code "14") (name "/col14") (class "Default")
      (node (ref "S214") (pin "2") (pinfunction "2_2") (pintype "passive"))
      (node (ref "S228") (pin "2") (pinfunction "2_2") (pintype "passive"))
      (node (ref "S259") (pin "2") (pinfunction "2_2") (pintype "passive"))
      (node (ref "S266") (pin "2") (pinfunction "2_2") (pintype "passive"))
      (node (ref "S269") (pin "2") (pinfunction "2_2") (pintype "passive"))
    )
    (net (code "15") (name "/row1") (class "Default")
      (node (ref "D201") (pin "2") (pinfunction "K_2") (pintype "passive"))
      (node (ref "D202") (pin "2") (pinfunction "K_2") (pintype "passive"))
      (node (ref "D203") (pin "2") (pinfunction "K_2") (pintype "passive"))
      (node (ref "D204") (pin "2") (pinfunction "K_2") (pintype "passive"))
      (node (ref "D205") (pin "2") (pinfunction "K_2") (pintype "passive"))
      (node (ref "D206") (pin "2") (pinfunction "K_2") (pintype "passive"))
      (node (ref "D207") (pin "2") (pinfunction "K_2") (pintype "passive"))
      (node (ref "D208") (pin "2") (pinfunction "K_2") (pintype "passive"))
      (node (ref "D209") (pin "2") (pinfunction "K_2") (pintype "passive"))
      (node (ref "D210") (pin "2") (pinfunction "K_2") (pintype "passive"))
      (node (ref "D211") (pin "2") (pinfunction "K_2") (pintype "passive"))
      (node (ref "D212") (pin "2") (pinfunction "K_2") (pintype "passive"))
      (node (ref "D213") (pin "2") (pinfunction "K_2") (pintype "passive"))
      (node (ref "D214") (pin "2") (pinfunction "K_2") (pintype "passive"))
    )
    (net (code "16") (name "/row2") (class "Default")
      (node (ref "D215") (pin "2") (pinfunction "K_2") (pintype "passive"))
      (node (ref "D216") (pin "2") (pinfunction "K_2") (pintype "passive"))
      (node (ref "D217") (pin "2") (pinfunction "K_2") (pintype "passive"))
      (node (ref "D218") (pin "2") (pinfunction "K_2") (pintype "passive"))
      (node (ref "D219") (pin "2") (pinfunction "K_2") (pintype "passive"))
      (node (ref "D220") (pin "2") (pinfunction "K_2") (pintype "passive"))
      (node (ref "D221") (pin "2") (pinfunction "K_2") (pintype "passive"))
      (node (ref "D222") (pin "2") (pinfunction "K_2") (pintype "passive"))
      (node (ref "D223") (pin "2") (pinfunction "K_2") (pintype "passive"))
      (node (ref "D224") (pin "2") (pinfunction "K_2") (pintype "passive"))
      (node (ref "D225") (pin "2") (pinfunction "K_2") (pintype "passive"))
      (node (ref "D226") (pin "2") (pinfunction "K_2") (pintype "passive"))
      (node (ref "D227") (pin "2") (pinfunction "K_2") (pintype "passive"))
      (node (ref "D259") (pin "2") (pinfunction "K_2") (pintype "passive"))
    )
    (net (code "17") (name "/row3") (class "Default")
      (node (ref "D228") (pin "2") (pinfunction "K_2") (pintype "passive"))
      (node (ref "D229") (pin "2") (pinfunction "K_2") (pintype "passive"))
      (node (ref "D230") (pin "2") (pinfunction "K_2") (pintype "passive"))
      (node (ref "D231") (pin "2") (pinfunction "K_2") (pintype "passive"))
      (node (ref "D232") (pin "2") (pinfunction "K_2") (pintype "passive"))
      (node (ref "D233") (pin "2") (pinfunction "K_2") (pintype "passive"))
      (node (ref "D234") (pin "2") (pinfunction "K_2") (pintype "passive"))
      (node (ref "D235") (pin "2") (pinfunction "K_2") (pintype "passive"))
      (node (ref "D236") (pin "2") (pinfunction "K_2") (pintype "passive"))
      (node (ref "D237") (pin "2") (pinfunction "K_2") (pintype "passive"))
      (node (ref "D238") (pin "2") (pinfunction "K_2") (pintype "passive"))
      (node (ref "D239") (pin "2") (pinfunction "K_2") (pintype "passive"))
      (node (ref "D240") (pin "2") (pinfunction "K_2") (pintype "passive"))
      (node (ref "D242") (pin "2") (pinfunction "K_2") (pintype "passive"))
    )
    (net (code "18") (name "/row4") (class "Default")
      (node (ref "D243") (pin "2") (pinfunction "K_2") (pintype "passive"))
      (node (ref "D244") (pin "2") (pinfunction "K_2") (pintype "passive"))
      (node (ref "D245") (pin "2") (pinfunction "K_2") (pintype "passive"))
      (node (ref "D246") (pin "2") (pinfunction "K_2") (pintype "passive"))
      (node (ref "D247") (pin "2") (pinfunction "K_2") (pintype "passive"))
      (node (ref "D248") (pin "2") (pinfunction "K_2") (pintype "passive"))
      (node (ref "D249") (pin "2") (pinfunction "K_2") (pintype "passive"))
      (node (ref "D250") (pin "2") (pinfunction "K_2") (pintype "passive"))
      (node (ref "D251") (pin "2") (pinfunction "K_2") (pintype "passive"))
      (node (ref "D252") (pin "2") (pinfunction "K_2") (pintype "passive"))
      (node (ref "D253") (pin "2") (pinfunction "K_2") (pintype "passive"))
      (node (ref "D254") (pin "2") (pinfunction "K_2") (pintype "passive"))
      (node (ref "D256") (pin "2") (pinfunction "K_2") (pintype "passive"))
      (node (ref "D269") (pin "2") (pinfunction "K_2") (pintype "passive"))
    )
    (net (code "19") (name "/row5") (class "Default")
      (node (ref "D257") (pin "2") (pinfunction "K_2") (pintype "passive"))
      (node (ref "D258") (pin "2") (pinfunction "K_2") (pintype "passive"))
      (node (ref "D260") (pin "2") (pinfunction "K_2") (pintype "passive"))
      (node (ref "D262") (pin "2") (pinfunction "K_2") (pintype "passive"))
      (node (ref "D264") (pin "2") (pinfunction "K_2") (pintype "passive"))
      (node (ref "D265") (pin "2") (pinfunction "K_2") (pintype "passive"))
      (node (ref "D266") (pin "2") (pinfunction "K_2") (pintype "passive"))
      (node (ref "D267") (pin "2") (pinfunction "K_2") (pintype "passive"))
      (node (ref "D268") (pin "2") (pinfunction "K_2") (pintype "passive"))
      (node (ref "D270") (pin "2") (pinfunction "K_2") (pintype "passive"))
    )
    (net (code "20") (name "Net-(D201-A)") (class "Default")
      (node (ref "D201") (pin "1") (pinfunction "A_1") (pintype "passive"))
      (node (ref "S201") (pin "1") (pinfunction "1_1") (pintype "passive"))
    )
    (net (code "21") (name "Net-(D202-A)") (class "Default")
      (node (ref "D202") (pin "1") (pinfunction "A_1") (pintype "passive"))
      (node (ref "S202") (pin "1") (pinfunction "1_1") (pintype "passive"))
    )
    (net (code "22") (name "Net-(D203-A)") (class "Default")
      (node (ref "D203") (pin "1") (pinfunction "A_1") (pintype "passive"))
      (node (ref "S203") (pin "1") (pinfunction "1_1") (pintype "passive"))
    )
    (net (code "23") (name "Net-(D204-A)") (class "Default")
      (node (ref "D204") (pin "1") (pinfunction "A_1") (pintype "passive"))
      (node (ref "S204") (pin "1") (pinfunction "1_1") (pintype "passive"))
    )
    (net (code "24") (name "Net-(D205-A)") (class "Default")
      (node (ref "D205") (pin "1") (pinfunction "A_1") (pintype "passive"))
      (node (ref "S205") (pin "1") (pinfunction "1_1") (pintype "passive"))
    )
    (net (code "25") (name "Net-(D206-A)") (class "Default")
      (node (ref "D206") (pin "1") (pinfunction "A_1") (pintype "passive"))
      (node (ref "S206") (pin "1") (pinfunction "1_1") (pintype "passive"))
    )
    (net (code "26") (name "Net-(D207-A)") (class "Default")
      (node (ref "D207") (pin "1") (pinfunction "A_1") (pintype "passive"))
      (node (ref "S207") (pin "1") (pinfunction "1_1") (pintype "passive"))
    )
    (net (code "27") (name "Net-(D208-A)") (class "Default")
      (node (ref "D208") (pin "1") (pinfunction "A_1") (pintype "passive"))
      (node (ref "S208") (pin "1") (pinfunction "1_1") (pintype "passive"))
    )
    (net (code "28") (name "Net-(D209-A)") (class "Default")
      (node (ref "D209") (pin "1") (pinfunction "A_1") (pintype "passive"))
      (node (ref "S209") (pin "1") (pinfunction "1_1") (pintype "passive"))
    )
    (net (code "29") (name "Net-(D210-A)") (class "Default")
      (node (ref "D210") (pin "1") (pinfunction "A_1") (pintype "passive"))
      (node (ref "S210") (pin "1") (pinfunction "1_1") (pintype "passive"))
    )
    (net (code "30") (name "Net-(D211-A)") (class "Default")
      (node (ref "D211") (pin "1") (pinfunction "A_1") (pintype "passive"))
      (node (ref "S211") (pin "1") (pinfunction "1_1") (pintype "passive"))
    )
    (net (code "31") (name "Net-(D212-A)") (class "Default")
      (node (ref "D212") (pin "1") (pinfunction "A_1") (pintype "passive"))
      (node (ref "S212") (pin "1") (pinfunction "1_1") (pintype "passive"))
    )
    (net (code "32") (name "Net-(D213-A)") (class "Default")
      (node (ref "D213") (pin "1") (pinfunction "A_1") (pintype "passive"))
      (node (ref "S213") (pin "1") (pinfunction "1_1") (pintype "passive"))
    )
    (net (code "33") (name "Net-(D214-A)") (class "Default")
      (node (ref "D214") (pin "1") (pinfunction "A_1") (pintype "passive"))
      (node (ref "S214") (pin "1") (pinfunction "1_1") (pintype "passive"))
    )
    (net (code "34") (name "Net-(D215-A)") (class "Default")
      (node (ref "D215") (pin "1") (pinfunction "A_1") (pintype "passive"))
      (node (ref "S215") (pin "1") (pinfunction "1_1") (pintype "passive"))
    )
    (net (code "35") (name "Net-(D216-A)") (class "Default")
      (node (ref "D216") (pin "1") (pinfunction "A_1") (pintype "passive"))
      (node (ref "S216") (pin "1") (pinfunction "1_1") (pintype "passive"))
    )
    (net (code "36") (name "Net-(D217-A)") (class "Default")
      (node (ref "D217") (pin "1") (pinfunction "A_1") (pintype "passive"))
      (node (ref "S217") (pin "1") (pinfunction "1_1") (pintype "passive"))
    )
    (net (code "37") (name "Net-(D218-A)") (class "Default")
      (node (ref "D218") (pin "1") (pinfunction "A_1") (pintype "passive"))
      (node (ref "S218") (pin "1") (pinfunction "1_1") (pintype "passive"))
    )
    (net (code "38") (name "Net-(D219-A)") (class "Default")
      (node (ref "D219") (pin "1") (pinfunction "A_1") (pintype "passive"))
      (node (ref "S219") (pin "1") (pinfunction "1_1") (pintype "passive"))
    )
    (net (code "39") (name "Net-(D220-A)") (class "Default")
      (node (ref "D220") (pin "1") (pinfunction "A_1") (pintype "passive"))
      (node (ref "S220") (pin "1") (pinfunction "1_1") (pintype "passive"))
    )
    (net (code "40") (name "Net-(D221-A)") (class "Default")
      (node (ref "D221") (pin "1") (pinfunction "A_1") (pintype "passive"))
      (node (ref "S221") (pin "1") (pinfunction "1_1") (pintype "passive"))
    )
    (net (code "41") (name "Net-(D222-A)") (class "Default")
      (node (ref "D222") (pin "1") (pinfunction "A_1") (pintype "passive"))
      (node (ref "S222") (pin "1") (pinfunction "1_1") (pintype "passive"))
    )
    (net (code "42") (name "Net-(D223-A)") (class "Default")
      (node (ref "D223") (pin "1") (pinfunction "A_1") (pintype "passive"))
      (node (ref "S223") (pin "1") (pinfunction "1_1") (pintype "passive"))
    )
    (net (code "43") (name "Net-(D224-A)") (class "Default")
      (node (ref "D224") (pin "1") (pinfunction "A_1") (pintype "passive"))
      (node (ref "S224") (pin "1") (pinfunction "1_1") (pintype "passive"))
    )
    (net (code "44") (name "Net-(D225-A)") (class "Default")
      (node (ref "D225") (pin "1") (pinfunction "A_1") (pintype "passive"))
      (node (ref "S225") (pin "1") (pinfunction "1_1") (pintype "passive"))
    )
    (net (code "45") (name "Net-(D226-A)") (class "Default")
      (node (ref "D226") (pin "1") (pinfunction "A_1") (pintype "passive"))
      (node (ref "S226") (pin "1") (pinfunction "1_1") (pintype "passive"))
    )
    (net (code "46") (name "Net-(D227-A)") (class "Default")
      (node (ref "D227") (pin "1") (pinfunction "A_1") (pintype "passive"))
      (node (ref "S227") (pin "1") (pinfunction "1_1") (pintype "passive"))
    )
    (net (code "47") (name "Net-(D228-A)") (class "Default")
      (node (ref "D228") (pin "1") (pinfunction "A_1") (pintype "passive"))
      (node (ref "S228") (pin "1") (pinfunction "1_1") (pintype "passive"))
    )
    (net (code "48") (name "Net-(D229-A)") (class "Default")
      (node (ref "D229") (pin "1") (pinfunction "A_1") (pintype "passive"))
      (node (ref "S229") (pin "1") (pinfunction "1_1") (pintype "passive"))
    )
    (net (code "49") (name "Net-(D230-A)") (class "Default")
      (node (ref "D230") (pin "1") (pinfunction "A_1") (pintype "passive"))
      (node (ref "S230") (pin "1") (pinfunction "1_1") (pintype "passive"))
    )
    (net (code "50") (name "Net-(D231-A)") (class "Default")
      (node (ref "D231") (pin "1") (pinfunction "A_1") (pintype "passive"))
      (node (ref "S231") (pin "1") (pinfunction "1_1") (pintype "passive"))
    )
    (net (code "51") (name "Net-(D232-A)") (class "Default")
      (node (ref "D232") (pin "1") (pinfunction "A_1") (pintype "passive"))
      (node (ref "S232") (pin "1") (pinfunction "1_1") (pintype "passive"))
    )
    (net (code "52") (name "Net-(D233-A)") (class "Default")
      (node (ref "D233") (pin "1") (pinfunction "A_1") (pintype "passive"))
      (node (ref "S233") (pin "1") (pinfunction "1_1") (pintype "passive"))
    )
    (net (code "53") (name "Net-(D234-A)") (class "Default")
      (node (ref "D234") (pin "1") (pinfunction "A_1") (pintype "passive"))
      (node (ref "S234") (pin "1") (pinfunction "1_1") (pintype "passive"))
    )
    (net (code "54") (name "Net-(D235-A)") (class "Default")
      (node (ref "D235") (pin "1") (pinfunction "A_1") (pintype "passive"))
      (node (ref "S235") (pin "1") (pinfunction "1_1") (pintype "passive"))
    )
    (net (code "55") (name "Net-(D236-A)") (class "Default")
      (node (ref "D236") (pin "1") (pinfunction "A_1") (pintype "passive"))
      (node (ref "S236") (pin "1") (pinfunction "1_1") (pintype "passive"))
    )
    (net (code "56") (name "Net-(D237-A)") (class "Default")
      (node (ref "D237") (pin "1") (pinfunction "A_1") (pintype "passive"))
      (node (ref "S237") (pin "1") (pinfunction "1_1") (pintype "passive"))
    )
    (net (code "57") (name "Net-(D238-A)") (class "Default")
      (node (ref "D238") (pin "1") (pinfunction "A_1") (pintype "passive"))
      (node (ref "S238") (pin "1") (pinfunction "1_1") (pintype "passive"))
    )
    (net (code "58") (name "Net-(D239-A)") (class "Default")
      (node (ref "D239") (pin "1") (pinfunction "A_1") (pintype "passive"))
      (node (ref "S239") (pin "1") (pinfunction "1_1") (pintype "passive"))
    )
    (net (code "59") (name "Net-(D240-A)") (class "Default")
      (node (ref "D240") (pin "1") (pinfunction "A_1") (pintype "passive"))
      (node (ref "S240") (pin "1") (pinfunction "1_1") (pintype "passive"))
    )
    (net (code "60") (name "Net-(D242-A)") (class "Default")
      (node (ref "D242") (pin "1") (pinfunction "A_1") (pintype "passive"))
      (node (ref "S242") (pin "1") (pinfunction "1_1") (pintype "passive"))
    )
    (net (code "61") (name "Net-(D243-A)") (class "Default")
      (node (ref "D243") (pin "1") (pinfunction "A_1") (pintype "passive"))
      (node (ref "S243") (pin "1") (pinfunction "1_1") (pintype "passive"))
    )
    (net (code "62") (name "Net-(D244-A)") (class "Default")
      (node (ref "D244") (pin "1") (pinfunction "A_1") (pintype "passive"))
      (node (ref "S244") (pin "1") (pinfunction "1_1") (pintype "passive"))
    )
    (net (code "63") (name "Net-(D245-A)") (class "Default")
      (node (ref "D245") (pin "1") (pinfunction "A_1") (pintype "passive"))
      (node (ref "S245") (pin "1") (pinfunction "1_1") (pintype "passive"))
    )
    (net (code "64") (name "Net-(D246-A)") (class "Default")
      (node (ref "D246") (pin "1") (pinfunction "A_1") (pintype "passive"))
      (node (ref "S246") (pin "1") (pinfunction "1_1") (pintype "passive"))
    )
    (net (code "65") (name "Net-(D247-A)") (class "Default")
      (node (ref "D247") (pin "1") (pinfunction "A_1") (pintype "passive"))
      (node (ref "S247") (pin "1") (pinfunction "1_1") (pintype "passive"))
    )
    (net (code "66") (name "Net-(D248-A)") (class "Default")
      (node (ref "D248") (pin "1") (pinfunction "A_1") (pintype "passive"))
      (node (ref "S248") (pin "1") (pinfunction "1_1") (pintype "passive"))
    )
    (net (code "67") (name "Net-(D249-A)") (class "Default")
      (node (ref "D249") (pin "1") (pinfunction "A_1") (pintype "passive"))
      (node (ref "S249") (pin "1") (pinfunction "1_1") (pintype "passive"))
    )
    (net (code "68") (name "Net-(D250-A)") (class "Default")
      (node (ref "D250") (pin "1") (pinfunction "A_1") (pintype "passive"))
      (node (ref "S250") (pin "1") (pinfunction "1_1") (pintype "passive"))
    )
    (net (code "69") (name "Net-(D251-A)") (class "Default")
      (node (ref "D251") (pin "1") (pinfunction "A_1") (pintype "passive"))
      (node (ref "S251") (pin "1") (pinfunction "1_1") (pintype "passive"))
    )
    (net (code "70") (name "Net-(D252-A)") (class "Default")
      (node (ref "D252") (pin "1") (pinfunction "A_1") (pintype "passive"))
      (node (ref "S252") (pin "1") (pinfunction "1_1") (pintype "passive"))
    )
    (net (code "71") (name "Net-(D253-A)") (class "Default")
      (node (ref "D253") (pin "1") (pinfunction "A_1") (pintype "passive"))
      (node (ref "S253") (pin "1") (pinfunction "1_1") (pintype "passive"))
    )
    (net (code "72") (name "Net-(D254-A)") (class "Default")
      (node (ref "D254") (pin "1") (pinfunction "A_1") (pintype "passive"))
      (node (ref "S254") (pin "1") (pinfunction "1_1") (pintype "passive"))
    )
    (net (code "73") (name "Net-(D256-A)") (class "Default")
      (node (ref "D256") (pin "1") (pinfunction "A_1") (pintype "passive"))
      (node (ref "S256") (pin "1") (pinfunction "1_1") (pintype "passive"))
    )
    (net (code "74") (name "Net-(D257-A)") (class "Default")
      (node (ref "D257") (pin "1") (pinfunction "A_1") (pintype "passive"))
      (node (ref "S257") (pin "1") (pinfunction "1_1") (pintype "passive"))
    )
    (net (code "75") (name "Net-(D258-A)") (class "Default")
      (node (ref "D258") (pin "1") (pinfunction "A_1") (pintype "passive"))
      (node (ref "S258") (pin "1") (pinfunction "1_1") (pintype "passive"))
    )
    (net (code "76") (name "Net-(D259-A)") (class "Default")
      (node (ref "D259") (pin "1") (pinfunction "A_1") (pintype "passive"))
      (node (ref "S259") (pin "1") (pinfunction "1_1") (pintype "passive"))
    )
    (net (code "77") (name "Net-(D260-A)") (class "Default")
      (node (ref "D260") (pin "1") (pinfunction "A_1") (pintype "passive"))
      (node (ref "S260") (pin "1") (pinfunction "1_1") (pintype "passive"))
    )
    (net (code "78") (name "Net-(D262-A)") (class "Default")
      (node (ref "D262") (pin "1") (pinfunction "A_1") (pintype "passive"))
      (node (ref "S262") (pin "1") (pinfunction "1_1") (pintype "passive"))
    )
    (net (code "79") (name "Net-(D264-A)") (class "Default")
      (node (ref "D264") (pin "1") (pinfunction "A_1") (pintype "passive"))
      (node (ref "S264") (pin "1") (pinfunction "1_1") (pintype "passive"))
    )
    (net (code "80") (name "Net-(D265-A)") (class "Default")
      (node (ref "D265") (pin "1") (pinfunction "A_1") (pintype "passive"))
      (node (ref "S265") (pin "1") (pinfunction "1_1") (pintype "passive"))
    )
    (net (code "81") (name "Net-(D266-A)") (class "Default")
      (node (ref "D266") (pin "1") (pinfunction "A_1") (pintype "passive"))
      (node (ref "S266") (pin "1") (pinfunction "1_1") (pintype "passive"))
    )
    (net (code "82") (name "Net-(D267-A)") (class "Default")
      (node (ref "D267") (pin "1") (pinfunction "A_1") (pintype "passive"))
      (node (ref "S267") (pin "1") (pinfunction "1_1") (pintype "passive"))
    )
    (net (code "83") (name "Net-(D268-A)") (class "Default")
      (node (ref "D268") (pin "1") (pinfunction "A_1") (pintype "passive"))
      (node (ref "S268") (pin "1") (pinfunction "1_1") (pintype "passive"))
    )
    (net (code "84") (name "Net-(D269-A)") (class "Default")
      (node (ref "D269") (pin "1") (pinfunction "A_1") (pintype "passive"))
      (node (ref "S269") (pin "1") (pinfunction "1_1") (pintype "passive"))
    )
    (net (code "85") (name "Net-(D270-A)") (class "Default")
      (node (ref "D270") (pin "1") (pinfunction "A_1") (pintype "passive"))
      (node (ref "S270") (pin "1") (pinfunction "1_1") (pintype "passive"))
    )
  )
)
